# V4-AddOnZigbee-SMD-V001.net
KiCad netlist of a schematic drawn in EAGLE
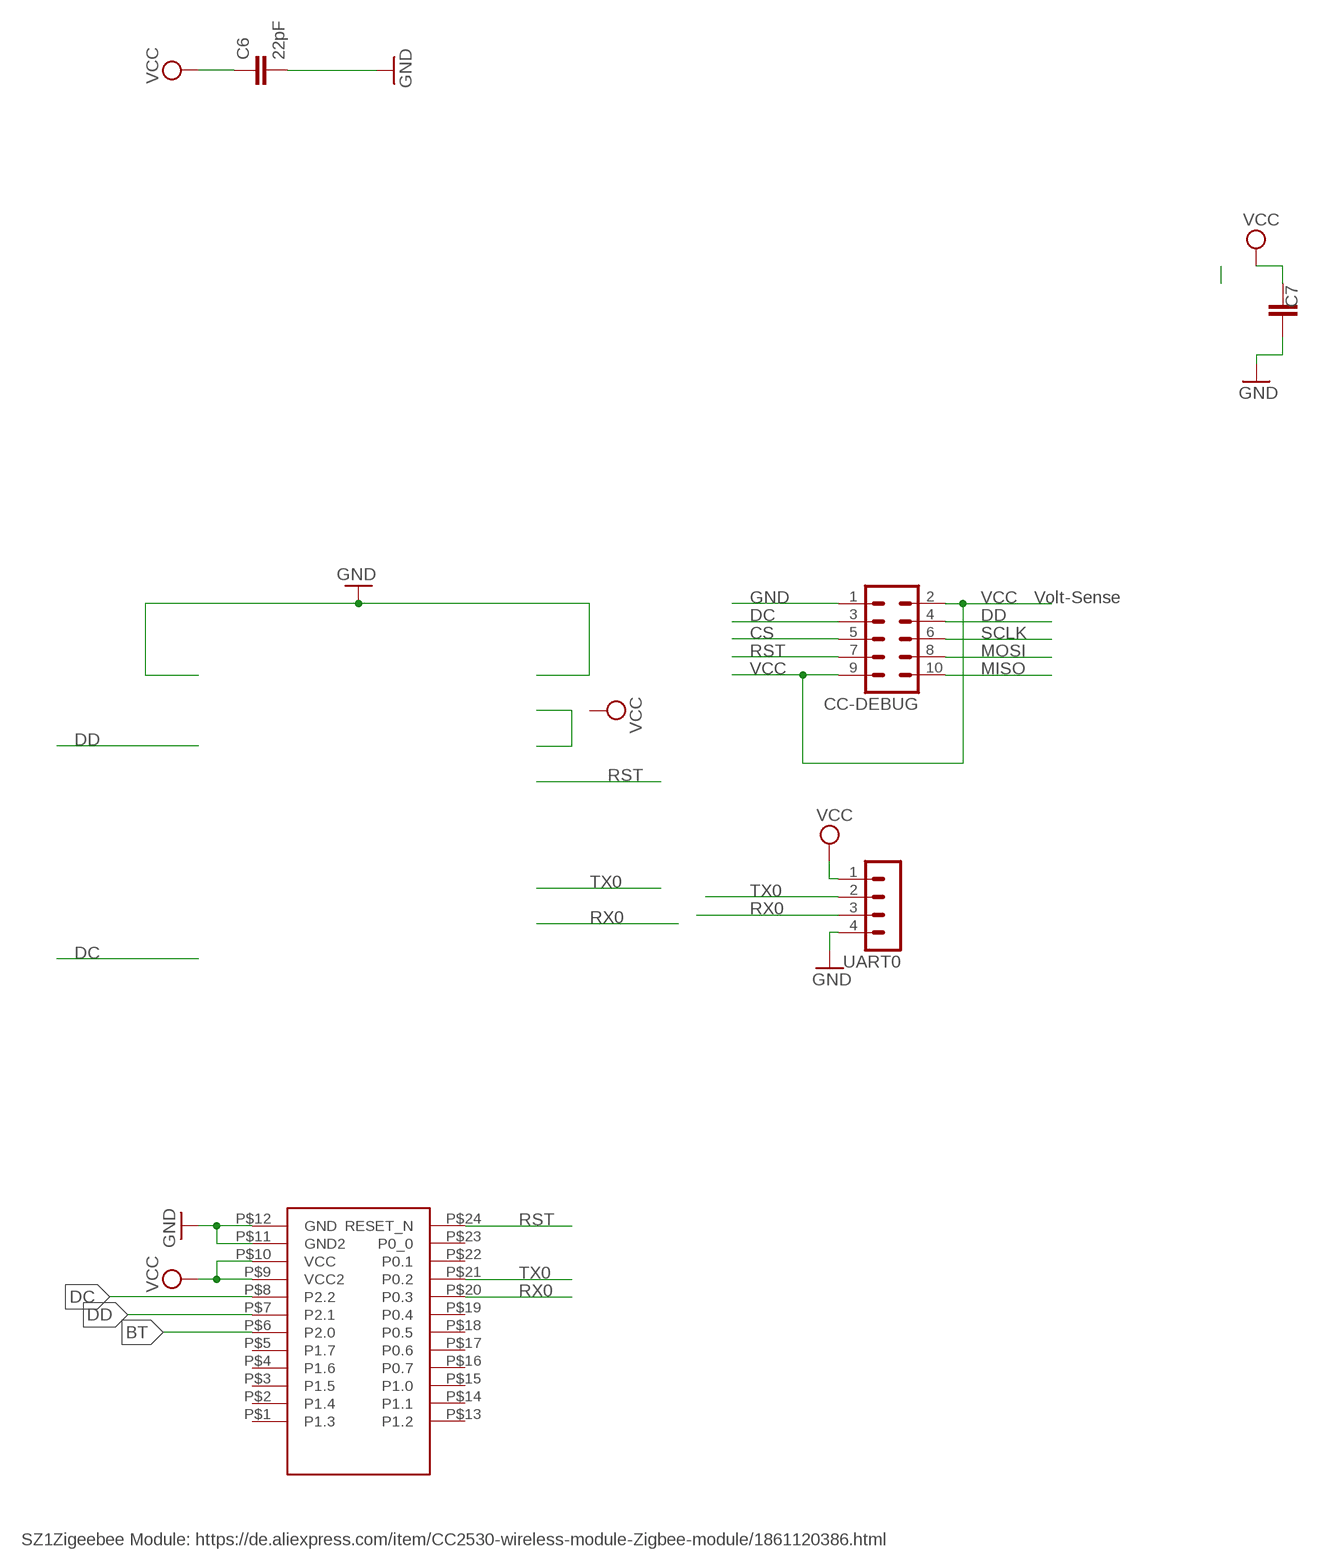
[diagram p0: schematic, sheet 1]

(export (version "E")
  (design (tool "Eeschema 10.0.6"))
  (components
    (comp (ref "C6")
      (value "22pF")
      (footprint "eagle-import:C0805")
      (libsource (lib "eagle-import") (part "C-EUC0805"))
    )
    (comp (ref "C7")
      (value "C-EUC1812")
      (footprint "eagle-import:C1812")
      (libsource (lib "eagle-import") (part "C-EUC1812"))
    )
    (comp (ref "CC-DEBUG")
      (value "MA05-2")
      (footprint "eagle-import:MA05-2")
      (libsource (lib "eagle-import") (part "MA05-2"))
    )
    (comp (ref "U$1")
      (value "CC2530CC2530PA")
      (footprint "eagle-import:CC2530PA")
      (libsource (lib "eagle-import") (part "CC2530CC2530PA"))
    )
    (comp (ref "UART0")
      (value "MA04-1")
      (footprint "eagle-import:MA04-1")
      (libsource (lib "eagle-import") (part "MA04-1"))
    )
  )
  (nets
    (net (code "1") (name "/CS") (class "Default")
      (node (ref "CC-DEBUG") (pin "5") (pinfunction "5_5") (pintype "passive"))
    )
    (net (code "2") (name "/MISO") (class "Default")
      (node (ref "CC-DEBUG") (pin "10") (pinfunction "10_10") (pintype "passive"))
    )
    (net (code "3") (name "/MOSI") (class "Default")
      (node (ref "CC-DEBUG") (pin "8") (pinfunction "8_8") (pintype "passive"))
    )
    (net (code "4") (name "/RST") (class "Default")
      (node (ref "CC-DEBUG") (pin "7") (pinfunction "7_7") (pintype "passive"))
      (node (ref "U$1") (pin "P$24") (pinfunction "RESET_N_P$24") (pintype "bidirectional"))
    )
    (net (code "5") (name "/RX0") (class "Default")
      (node (ref "U$1") (pin "P$20") (pinfunction "P0.3_P$20") (pintype "bidirectional"))
      (node (ref "UART0") (pin "3") (pinfunction "3_3") (pintype "passive"))
    )
    (net (code "6") (name "/SCLK") (class "Default")
      (node (ref "CC-DEBUG") (pin "6") (pinfunction "6_6") (pintype "passive"))
    )
    (net (code "7") (name "/TX0") (class "Default")
      (node (ref "U$1") (pin "P$21") (pinfunction "P0.2_P$21") (pintype "bidirectional"))
      (node (ref "UART0") (pin "2") (pinfunction "2_2") (pintype "passive"))
    )
    (net (code "8") (name "BT") (class "Default")
      (node (ref "U$1") (pin "P$6") (pinfunction "P2.0_P$6") (pintype "bidirectional"))
    )
    (net (code "9") (name "DC") (class "Default")
      (node (ref "CC-DEBUG") (pin "3") (pinfunction "3_3") (pintype "passive"))
      (node (ref "U$1") (pin "P$8") (pinfunction "P2.2_P$8") (pintype "bidirectional"))
    )
    (net (code "10") (name "DD") (class "Default")
      (node (ref "CC-DEBUG") (pin "4") (pinfunction "4_4") (pintype "passive"))
      (node (ref "U$1") (pin "P$7") (pinfunction "P2.1_P$7") (pintype "bidirectional"))
    )
    (net (code "11") (name "GND") (class "Default")
      (node (ref "C6") (pin "2") (pinfunction "2_2") (pintype "passive"))
      (node (ref "C7") (pin "1") (pinfunction "1_1") (pintype "passive"))
      (node (ref "CC-DEBUG") (pin "1") (pinfunction "1_1") (pintype "passive"))
      (node (ref "U$1") (pin "P$11") (pinfunction "GND2_P$11") (pintype "bidirectional"))
      (node (ref "U$1") (pin "P$12") (pinfunction "GND_P$12") (pintype "bidirectional"))
      (node (ref "UART0") (pin "4") (pinfunction "4_4") (pintype "passive"))
    )
    (net (code "12") (name "VCC") (class "Default")
      (node (ref "C6") (pin "1") (pinfunction "1_1") (pintype "passive"))
      (node (ref "C7") (pin "2") (pinfunction "2_2") (pintype "passive"))
      (node (ref "CC-DEBUG") (pin "2") (pinfunction "2_2") (pintype "passive"))
      (node (ref "CC-DEBUG") (pin "9") (pinfunction "9_9") (pintype "passive"))
      (node (ref "U$1") (pin "P$10") (pinfunction "VCC_P$10") (pintype "bidirectional"))
      (node (ref "U$1") (pin "P$9") (pinfunction "VCC2_P$9") (pintype "bidirectional"))
      (node (ref "UART0") (pin "1") (pinfunction "1_1") (pintype "passive"))
    )
    (net (code "13") (name "unconnected-(U$1-P0.1-PadP$22)") (class "Default")
      (node (ref "U$1") (pin "P$22") (pinfunction "P0.1_P$22") (pintype "bidirectional"))
    )
    (net (code "14") (name "unconnected-(U$1-P0.4-PadP$19)") (class "Default")
      (node (ref "U$1") (pin "P$19") (pinfunction "P0.4_P$19") (pintype "bidirectional"))
    )
    (net (code "15") (name "unconnected-(U$1-P0.5-PadP$18)") (class "Default")
      (node (ref "U$1") (pin "P$18") (pinfunction "P0.5_P$18") (pintype "bidirectional"))
    )
    (net (code "16") (name "unconnected-(U$1-P0.6-PadP$17)") (class "Default")
      (node (ref "U$1") (pin "P$17") (pinfunction "P0.6_P$17") (pintype "bidirectional"))
    )
    (net (code "17") (name "unconnected-(U$1-P0.7-PadP$16)") (class "Default")
      (node (ref "U$1") (pin "P$16") (pinfunction "P0.7_P$16") (pintype "bidirectional"))
    )
    (net (code "18") (name "unconnected-(U$1-P0_0-PadP$23)") (class "Default")
      (node (ref "U$1") (pin "P$23") (pinfunction "P0_0_P$23") (pintype "bidirectional"))
    )
    (net (code "19") (name "unconnected-(U$1-P1.0-PadP$15)") (class "Default")
      (node (ref "U$1") (pin "P$15") (pinfunction "P1.0_P$15") (pintype "bidirectional"))
    )
    (net (code "20") (name "unconnected-(U$1-P1.1-PadP$14)") (class "Default")
      (node (ref "U$1") (pin "P$14") (pinfunction "P1.1_P$14") (pintype "bidirectional"))
    )
    (net (code "21") (name "unconnected-(U$1-P1.2-PadP$13)") (class "Default")
      (node (ref "U$1") (pin "P$13") (pinfunction "P1.2_P$13") (pintype "bidirectional"))
    )
    (net (code "22") (name "unconnected-(U$1-P1.3-PadP$1)") (class "Default")
      (node (ref "U$1") (pin "P$1") (pinfunction "P1.3_P$1") (pintype "bidirectional"))
    )
    (net (code "23") (name "unconnected-(U$1-P1.4-PadP$2)") (class "Default")
      (node (ref "U$1") (pin "P$2") (pinfunction "P1.4_P$2") (pintype "bidirectional"))
    )
    (net (code "24") (name "unconnected-(U$1-P1.5-PadP$3)") (class "Default")
      (node (ref "U$1") (pin "P$3") (pinfunction "P1.5_P$3") (pintype "bidirectional"))
    )
    (net (code "25") (name "unconnected-(U$1-P1.6-PadP$4)") (class "Default")
      (node (ref "U$1") (pin "P$4") (pinfunction "P1.6_P$4") (pintype "bidirectional"))
    )
    (net (code "26") (name "unconnected-(U$1-P1.7-PadP$5)") (class "Default")
      (node (ref "U$1") (pin "P$5") (pinfunction "P1.7_P$5") (pintype "bidirectional"))
    )
  )
)
